# ADC.net
KiCad netlist of a schematic drawn in EAGLE
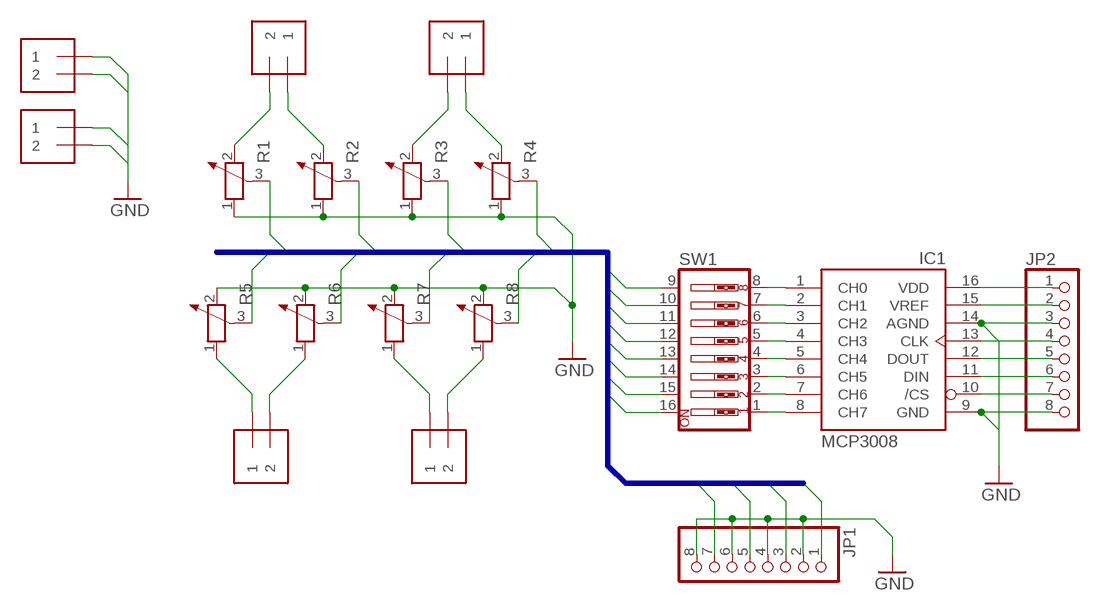
[diagram p0: schematic, sheet 1]

(export (version "E")
  (design (tool "Eeschema 10.0.6"))
  (components
    (comp (ref "IC1")
      (value "MCP3008")
      (footprint "eagle-import:DIL16")
      (libsource (lib "eagle-import") (part "MCP3008"))
    )
    (comp (ref "J1")
      (value "1X2-3.5MM")
      (footprint "eagle-import:1X2-3.5MM")
      (libsource (lib "eagle-import") (part "1X2-3.5MM"))
    )
    (comp (ref "J2")
      (value "1X2-3.5MM")
      (footprint "eagle-import:1X2-3.5MM")
      (libsource (lib "eagle-import") (part "1X2-3.5MM"))
    )
    (comp (ref "J3")
      (value "1X2-3.5MM")
      (footprint "eagle-import:1X2-3.5MM")
      (libsource (lib "eagle-import") (part "1X2-3.5MM"))
    )
    (comp (ref "J4")
      (value "1X2-3.5MM")
      (footprint "eagle-import:1X2-3.5MM")
      (libsource (lib "eagle-import") (part "1X2-3.5MM"))
    )
    (comp (ref "J5")
      (value "1X2-3.5MM")
      (footprint "eagle-import:1X2-3.5MM")
      (libsource (lib "eagle-import") (part "1X2-3.5MM"))
    )
    (comp (ref "J6")
      (value "1X2-3.5MM")
      (footprint "eagle-import:1X2-3.5MM")
      (libsource (lib "eagle-import") (part "1X2-3.5MM"))
    )
    (comp (ref "JP1")
      (value "PINHD-1X8CLEANBIG")
      (footprint "eagle-import:1X08-CLEANBIG")
      (libsource (lib "eagle-import") (part "PINHD-1X8CLEANBIG"))
    )
    (comp (ref "JP2")
      (value "PINHD-1X8CLEANBIG")
      (footprint "eagle-import:1X08-CLEANBIG")
      (libsource (lib "eagle-import") (part "PINHD-1X8CLEANBIG"))
    )
    (comp (ref "R1")
      (value "POTENTIOMETER_PT-10")
      (footprint "eagle-import:PT-10")
      (libsource (lib "eagle-import") (part "POTENTIOMETER_PT-10"))
    )
    (comp (ref "R2")
      (value "POTENTIOMETER_PT-10")
      (footprint "eagle-import:PT-10")
      (libsource (lib "eagle-import") (part "POTENTIOMETER_PT-10"))
    )
    (comp (ref "R3")
      (value "POTENTIOMETER_PT-10")
      (footprint "eagle-import:PT-10")
      (libsource (lib "eagle-import") (part "POTENTIOMETER_PT-10"))
    )
    (comp (ref "R4")
      (value "POTENTIOMETER_PT-10")
      (footprint "eagle-import:PT-10")
      (libsource (lib "eagle-import") (part "POTENTIOMETER_PT-10"))
    )
    (comp (ref "R5")
      (value "POTENTIOMETER_PT-10")
      (footprint "eagle-import:PT-10")
      (libsource (lib "eagle-import") (part "POTENTIOMETER_PT-10"))
    )
    (comp (ref "R6")
      (value "POTENTIOMETER_PT-10")
      (footprint "eagle-import:PT-10")
      (libsource (lib "eagle-import") (part "POTENTIOMETER_PT-10"))
    )
    (comp (ref "R7")
      (value "POTENTIOMETER_PT-10")
      (footprint "eagle-import:PT-10")
      (libsource (lib "eagle-import") (part "POTENTIOMETER_PT-10"))
    )
    (comp (ref "R8")
      (value "POTENTIOMETER_PT-10")
      (footprint "eagle-import:PT-10")
      (libsource (lib "eagle-import") (part "POTENTIOMETER_PT-10"))
    )
    (comp (ref "SW1")
      (value "SW_DIP-8")
      (footprint "eagle-import:EDG-08")
      (libsource (lib "eagle-import") (part "SW_DIP-8"))
    )
  )
  (nets
    (net (code "1") (name "/B$1") (class "Default")
      (node (ref "JP1") (pin "1") (pinfunction "1_1") (pintype "passive"))
      (node (ref "JP1") (pin "3") (pinfunction "3_3") (pintype "passive"))
      (node (ref "JP1") (pin "5") (pinfunction "5_5") (pintype "passive"))
      (node (ref "JP1") (pin "7") (pinfunction "7_7") (pintype "passive"))
      (node (ref "R1") (pin "3") (pinfunction "3_3") (pintype "passive"))
      (node (ref "R2") (pin "3") (pinfunction "3_3") (pintype "passive"))
      (node (ref "R3") (pin "3") (pinfunction "3_3") (pintype "passive"))
      (node (ref "R4") (pin "3") (pinfunction "3_3") (pintype "passive"))
      (node (ref "R5") (pin "3") (pinfunction "3_3") (pintype "passive"))
      (node (ref "R6") (pin "3") (pinfunction "3_3") (pintype "passive"))
      (node (ref "R7") (pin "3") (pinfunction "3_3") (pintype "passive"))
      (node (ref "R8") (pin "3") (pinfunction "3_3") (pintype "passive"))
      (node (ref "SW1") (pin "10") (pinfunction "10_10") (pintype "passive"))
      (node (ref "SW1") (pin "11") (pinfunction "11_11") (pintype "passive"))
      (node (ref "SW1") (pin "12") (pinfunction "12_12") (pintype "passive"))
      (node (ref "SW1") (pin "13") (pinfunction "13_13") (pintype "passive"))
      (node (ref "SW1") (pin "14") (pinfunction "14_14") (pintype "passive"))
      (node (ref "SW1") (pin "15") (pinfunction "15_15") (pintype "passive"))
      (node (ref "SW1") (pin "16") (pinfunction "16_16") (pintype "passive"))
      (node (ref "SW1") (pin "9") (pinfunction "9_9") (pintype "passive"))
    )
    (net (code "2") (name "GND") (class "Default")
      (node (ref "IC1") (pin "14") (pinfunction "AGND_14") (pintype "power_in"))
      (node (ref "IC1") (pin "9") (pinfunction "GND_9") (pintype "power_in"))
      (node (ref "J5") (pin "1") (pinfunction "1_1") (pintype "passive"))
      (node (ref "J5") (pin "2") (pinfunction "2_2") (pintype "passive"))
      (node (ref "J6") (pin "1") (pinfunction "1_1") (pintype "passive"))
      (node (ref "J6") (pin "2") (pinfunction "2_2") (pintype "passive"))
      (node (ref "JP1") (pin "2") (pinfunction "2_2") (pintype "passive"))
      (node (ref "JP1") (pin "4") (pinfunction "4_4") (pintype "passive"))
      (node (ref "JP1") (pin "6") (pinfunction "6_6") (pintype "passive"))
      (node (ref "JP1") (pin "8") (pinfunction "8_8") (pintype "passive"))
      (node (ref "JP2") (pin "3") (pinfunction "3_3") (pintype "passive"))
      (node (ref "JP2") (pin "8") (pinfunction "8_8") (pintype "passive"))
      (node (ref "R1") (pin "1") (pinfunction "1_1") (pintype "passive"))
      (node (ref "R2") (pin "1") (pinfunction "1_1") (pintype "passive"))
      (node (ref "R3") (pin "1") (pinfunction "1_1") (pintype "passive"))
      (node (ref "R4") (pin "1") (pinfunction "1_1") (pintype "passive"))
      (node (ref "R5") (pin "2") (pinfunction "2_2") (pintype "passive"))
      (node (ref "R6") (pin "2") (pinfunction "2_2") (pintype "passive"))
      (node (ref "R7") (pin "2") (pinfunction "2_2") (pintype "passive"))
      (node (ref "R8") (pin "2") (pinfunction "2_2") (pintype "passive"))
    )
    (net (code "3") (name "Net-(IC1-CH0)") (class "Default")
      (node (ref "IC1") (pin "1") (pinfunction "CH0_1") (pintype "input"))
      (node (ref "SW1") (pin "8") (pinfunction "8_8") (pintype "passive"))
    )
    (net (code "4") (name "Net-(IC1-CH1)") (class "Default")
      (node (ref "IC1") (pin "2") (pinfunction "CH1_2") (pintype "input"))
      (node (ref "SW1") (pin "7") (pinfunction "7_7") (pintype "passive"))
    )
    (net (code "5") (name "Net-(IC1-CH2)") (class "Default")
      (node (ref "IC1") (pin "3") (pinfunction "CH2_3") (pintype "input"))
      (node (ref "SW1") (pin "6") (pinfunction "6_6") (pintype "passive"))
    )
    (net (code "6") (name "Net-(IC1-CH3)") (class "Default")
      (node (ref "IC1") (pin "4") (pinfunction "CH3_4") (pintype "input"))
      (node (ref "SW1") (pin "5") (pinfunction "5_5") (pintype "passive"))
    )
    (net (code "7") (name "Net-(IC1-CH4)") (class "Default")
      (node (ref "IC1") (pin "5") (pinfunction "CH4_5") (pintype "input"))
      (node (ref "SW1") (pin "4") (pinfunction "4_4") (pintype "passive"))
    )
    (net (code "8") (name "Net-(IC1-CH5)") (class "Default")
      (node (ref "IC1") (pin "6") (pinfunction "CH5_6") (pintype "input"))
      (node (ref "SW1") (pin "3") (pinfunction "3_3") (pintype "passive"))
    )
    (net (code "9") (name "Net-(IC1-CH6)") (class "Default")
      (node (ref "IC1") (pin "7") (pinfunction "CH6_7") (pintype "input"))
      (node (ref "SW1") (pin "2") (pinfunction "2_2") (pintype "passive"))
    )
    (net (code "10") (name "Net-(IC1-CH7)") (class "Default")
      (node (ref "IC1") (pin "8") (pinfunction "CH7_8") (pintype "input"))
      (node (ref "SW1") (pin "1") (pinfunction "1_1") (pintype "passive"))
    )
    (net (code "11") (name "Net-(IC1-CLK)") (class "Default")
      (node (ref "IC1") (pin "13") (pinfunction "CLK_13") (pintype "input"))
      (node (ref "JP2") (pin "4") (pinfunction "4_4") (pintype "passive"))
    )
    (net (code "12") (name "Net-(IC1-DIN)") (class "Default")
      (node (ref "IC1") (pin "11") (pinfunction "DIN_11") (pintype "input"))
      (node (ref "JP2") (pin "6") (pinfunction "6_6") (pintype "passive"))
    )
    (net (code "13") (name "Net-(IC1-DOUT)") (class "Default")
      (node (ref "IC1") (pin "12") (pinfunction "DOUT_12") (pintype "output"))
      (node (ref "JP2") (pin "5") (pinfunction "5_5") (pintype "passive"))
    )
    (net (code "14") (name "Net-(IC1-VDD)") (class "Default")
      (node (ref "IC1") (pin "16") (pinfunction "VDD_16") (pintype "power_in"))
      (node (ref "JP2") (pin "1") (pinfunction "1_1") (pintype "passive"))
    )
    (net (code "15") (name "Net-(IC1-VREF)") (class "Default")
      (node (ref "IC1") (pin "15") (pinfunction "VREF_15") (pintype "input"))
      (node (ref "JP2") (pin "2") (pinfunction "2_2") (pintype "passive"))
    )
    (net (code "16") (name "Net-(IC1-{slash}CS)") (class "Default")
      (node (ref "IC1") (pin "10") (pinfunction "/CS_10") (pintype "input"))
      (node (ref "JP2") (pin "7") (pinfunction "7_7") (pintype "passive"))
    )
    (net (code "17") (name "Net-(J1-Pad1)") (class "Default")
      (node (ref "J1") (pin "1") (pinfunction "1_1") (pintype "passive"))
      (node (ref "R4") (pin "2") (pinfunction "2_2") (pintype "passive"))
    )
    (net (code "18") (name "Net-(J1-Pad2)") (class "Default")
      (node (ref "J1") (pin "2") (pinfunction "2_2") (pintype "passive"))
      (node (ref "R3") (pin "2") (pinfunction "2_2") (pintype "passive"))
    )
    (net (code "19") (name "Net-(J2-Pad1)") (class "Default")
      (node (ref "J2") (pin "1") (pinfunction "1_1") (pintype "passive"))
      (node (ref "R2") (pin "2") (pinfunction "2_2") (pintype "passive"))
    )
    (net (code "20") (name "Net-(J2-Pad2)") (class "Default")
      (node (ref "J2") (pin "2") (pinfunction "2_2") (pintype "passive"))
      (node (ref "R1") (pin "2") (pinfunction "2_2") (pintype "passive"))
    )
    (net (code "21") (name "Net-(J3-Pad1)") (class "Default")
      (node (ref "J3") (pin "1") (pinfunction "1_1") (pintype "passive"))
      (node (ref "R5") (pin "1") (pinfunction "1_1") (pintype "passive"))
    )
    (net (code "22") (name "Net-(J3-Pad2)") (class "Default")
      (node (ref "J3") (pin "2") (pinfunction "2_2") (pintype "passive"))
      (node (ref "R6") (pin "1") (pinfunction "1_1") (pintype "passive"))
    )
    (net (code "23") (name "Net-(J4-Pad1)") (class "Default")
      (node (ref "J4") (pin "1") (pinfunction "1_1") (pintype "passive"))
      (node (ref "R7") (pin "1") (pinfunction "1_1") (pintype "passive"))
    )
    (net (code "24") (name "Net-(J4-Pad2)") (class "Default")
      (node (ref "J4") (pin "2") (pinfunction "2_2") (pintype "passive"))
      (node (ref "R8") (pin "1") (pinfunction "1_1") (pintype "passive"))
    )
  )
)
